# eboardPapyFeederV2_1.net
KiCad netlist of a schematic drawn in Altium Designer
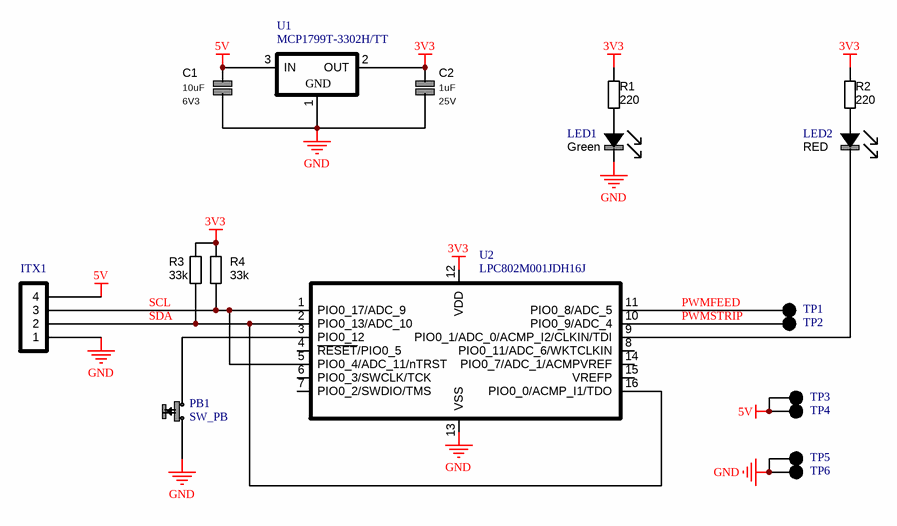
[diagram p0: eboardPapyFeederV2.1.SchDoc]

(export (version "E")
  (design (tool "Eeschema 10.0.6"))
  (components
    (comp (ref "C1")
      (value "10uF")
      (footprint "0603_CAP")
      (description "CAP CER 10UF 6V3 X5R 0603")
      (fields
        (field (name "VOLTAGE") "6V3")
        (field (name "MANUFACTURER") "Murata Electronics North America")
        (field (name "MANUFACTURER PART NUMBER") "GRM188R60J106ME84J")
      )
      (libsource (lib "Database_Library") (part "CAP"))
    )
    (comp (ref "C2")
      (value "1uF")
      (footprint "0603_CAP")
      (description "CAP CER 1uF 25V X5R 0603")
      (fields
        (field (name "VOLTAGE") "25V")
        (field (name "MANUFACTURER") "YAGEO")
        (field (name "MANUFACTURER PART NUMBER") "CC0603KRX5R8BB105")
      )
      (libsource (lib "Database_Library") (part "CAP"))
    )
    (comp (ref "ITX1")
      (value "Header 01X04")
      (footprint "HEADER_1X4_2MM_SPRING_01")
      (description "4POS spring connector")
      (fields (field (name "MANUFACTURER") "MOLEX") (field (name "MANUFACTURER PART NUMBER") "472861001"))
      (libsource (lib "Database_Library") (part "Header 01X04"))
    )
    (comp (ref "LED1")
      (value "Green")
      (footprint "0603_LED")
      (description "LED Green 0603")
      (fields
        (field (name "COLOR") "Green")
        (field (name "MANUFACTURER") "Dialight")
        (field (name "MANUFACTURER PART NUMBER") "599-0081-007F")
      )
      (libsource (lib "Database_Library") (part "LED"))
    )
    (comp (ref "LED2")
      (value "RED")
      (footprint "0603_LED")
      (description "LED RED 0603")
      (fields
        (field (name "COLOR") "RED")
        (field (name "MANUFACTURER") "Dialight")
        (field (name "MANUFACTURER PART NUMBER") "599-0010-007F")
      )
      (libsource (lib "Database_Library") (part "LED"))
    )
    (comp (ref "PB1")
      (value "SW_PB")
      (footprint "SKRPABE010")
      (description "Mini momentary push button")
      (fields (field (name "MANUFACTURER") "ALPS") (field (name "MANUFACTURER PART NUMBER") "SKRPABE010"))
      (libsource (lib "Database_Library") (part "SW_PB"))
    )
    (comp (ref "R1")
      (value "220")
      (footprint "0603_RES")
      (description "RES SMD 220 OHM 1% 1/10W 0603")
      (fields
        (field (name "MANUFACTURER") "Panasonic Electronic Components")
        (field (name "MANUFACTURER PART NUMBER") "ERJ-3EKF2200V")
      )
      (libsource (lib "Database_Library") (part "RES"))
    )
    (comp (ref "R2")
      (value "220")
      (footprint "0603_RES")
      (description "RES SMD 220 OHM 1% 1/10W 0603")
      (fields
        (field (name "MANUFACTURER") "Panasonic Electronic Components")
        (field (name "MANUFACTURER PART NUMBER") "ERJ-3EKF2200V")
      )
      (libsource (lib "Database_Library") (part "RES"))
    )
    (comp (ref "R3")
      (value "33k")
      (footprint "0603_RES")
      (description "RES SMD 33K OHM 1% 1/10W 0603")
      (fields
        (field (name "MANUFACTURER") "Panasonic Electronic Components")
        (field (name "MANUFACTURER PART NUMBER") "ERJ-3EKF3302V")
      )
      (libsource (lib "Database_Library") (part "RES"))
    )
    (comp (ref "R4")
      (value "33k")
      (footprint "0603_RES")
      (description "RES SMD 33K OHM 1% 1/10W 0603")
      (fields
        (field (name "MANUFACTURER") "Panasonic Electronic Components")
        (field (name "MANUFACTURER PART NUMBER") "ERJ-3EKF3302V")
      )
      (libsource (lib "Database_Library") (part "RES"))
    )
    (comp (ref "TP1")
      (value "TP")
      (footprint "PAD_TOP_1x5_REC")
      (description "PAD_1x5_REC")
      (fields (field (name "MANUFACTURER") "None"))
      (libsource (lib "Database_Library") (part "TP"))
    )
    (comp (ref "TP2")
      (value "TP")
      (footprint "PAD_TOP_1x5_REC")
      (description "PAD_1x5_REC")
      (fields (field (name "MANUFACTURER") "None"))
      (libsource (lib "Database_Library") (part "TP"))
    )
    (comp (ref "TP3")
      (value "TP")
      (footprint "PAD_TOP_1x5_REC")
      (description "PAD_1x5_REC")
      (fields (field (name "MANUFACTURER") "None"))
      (libsource (lib "Database_Library") (part "TP"))
    )
    (comp (ref "TP4")
      (value "TP")
      (footprint "PAD_TOP_1x5_REC")
      (description "PAD_1x5_REC")
      (fields (field (name "MANUFACTURER") "None"))
      (libsource (lib "Database_Library") (part "TP"))
    )
    (comp (ref "TP5")
      (value "TP")
      (footprint "PAD_TOP_1x5_REC")
      (description "PAD_1x5_REC")
      (fields (field (name "MANUFACTURER") "None"))
      (libsource (lib "Database_Library") (part "TP"))
    )
    (comp (ref "TP6")
      (value "TP")
      (footprint "PAD_TOP_1x5_REC")
      (description "PAD_1x5_REC")
      (fields (field (name "MANUFACTURER") "None"))
      (libsource (lib "Database_Library") (part "TP"))
    )
    (comp (ref "U1")
      (value "3P-Fixed_GND_VOUT_VIN")
      (footprint "SOT95P237X112-3N")
      (description "LDO 3V3 80mA")
      (fields
        (field (name "MANUFACTURER") "MICROCHIP")
        (field (name "MANUFACTURER PART NUMBER") "MCP1799T-3302H/TT")
      )
      (libsource (lib "Database_Library") (part "3P-Fixed_GND_VOUT_VIN"))
    )
    (comp (ref "U2")
      (value "LPC802M001JDH16J")
      (footprint "SOP65P640X110-16M")
      (description "ARM Cortex M0+")
      (fields (field (name "MANUFACTURER") "NXP") (field (name "VOLTAGE") "3.3V"))
      (libsource (lib "Database_Library") (part "LPC802M001JDH16J"))
    )
  )
  (nets
    (net (code "1") (name "/PWMFEED") (class "Default")
      (node (ref "TP1") (pin "1") (pintype "passive"))
      (node (ref "U2") (pin "11") (pinfunction "PIO0_8/ADC_5_11") (pintype "passive"))
    )
    (net (code "2") (name "/PWMSTRIP") (class "Default")
      (node (ref "TP2") (pin "1") (pintype "passive"))
      (node (ref "U2") (pin "10") (pinfunction "PIO0_9/ADC_4_10") (pintype "passive"))
    )
    (net (code "3") (name "/SCL") (class "Default")
      (node (ref "ITX1") (pin "3") (pinfunction "3_3") (pintype "passive"))
      (node (ref "R4") (pin "1") (pinfunction "1_1") (pintype "passive"))
      (node (ref "U2") (pin "1") (pinfunction "PIO0_17/ADC_9_1") (pintype "passive"))
      (node (ref "U2") (pin "5") (pinfunction "PIO0_4/ADC_11/nTRST_5") (pintype "passive"))
    )
    (net (code "4") (name "/SDA") (class "Default")
      (node (ref "ITX1") (pin "2") (pinfunction "2_2") (pintype "passive"))
      (node (ref "R3") (pin "1") (pinfunction "1_1") (pintype "passive"))
      (node (ref "U2") (pin "16") (pinfunction "PIO0_0/ACMP_I1/TDO_16") (pintype "passive"))
      (node (ref "U2") (pin "2") (pinfunction "PIO0_13/ADC_10_2") (pintype "passive"))
    )
    (net (code "5") (name "3V3") (class "Default")
      (node (ref "C2") (pin "1") (pinfunction "1_1") (pintype "passive"))
      (node (ref "R1") (pin "2") (pinfunction "2_2") (pintype "passive"))
      (node (ref "R2") (pin "2") (pinfunction "2_2") (pintype "passive"))
      (node (ref "R3") (pin "2") (pinfunction "2_2") (pintype "passive"))
      (node (ref "R4") (pin "2") (pinfunction "2_2") (pintype "passive"))
      (node (ref "U1") (pin "2") (pinfunction "OUT_2") (pintype "power_in"))
      (node (ref "U2") (pin "12") (pinfunction "VDD_12") (pintype "passive"))
    )
    (net (code "6") (name "5V") (class "Default")
      (node (ref "C1") (pin "1") (pinfunction "1_1") (pintype "passive"))
      (node (ref "ITX1") (pin "4") (pinfunction "4_4") (pintype "passive"))
      (node (ref "TP3") (pin "1") (pintype "passive"))
      (node (ref "TP4") (pin "1") (pintype "passive"))
      (node (ref "U1") (pin "3") (pinfunction "IN_3") (pintype "power_in"))
    )
    (net (code "7") (name "GND") (class "Default")
      (node (ref "C1") (pin "2") (pinfunction "2_2") (pintype "passive"))
      (node (ref "C2") (pin "2") (pinfunction "2_2") (pintype "passive"))
      (node (ref "ITX1") (pin "1") (pinfunction "1_1") (pintype "passive"))
      (node (ref "LED1") (pin "2") (pinfunction "K_2") (pintype "passive"))
      (node (ref "PB1") (pin "1") (pintype "passive"))
      (node (ref "TP5") (pin "1") (pintype "passive"))
      (node (ref "TP6") (pin "1") (pintype "passive"))
      (node (ref "U1") (pin "1") (pinfunction "GND_1") (pintype "power_in"))
      (node (ref "U2") (pin "13") (pinfunction "VSS_13") (pintype "passive"))
    )
    (net (code "8") (name "Net-(LED1-A)") (class "Default")
      (node (ref "LED1") (pin "1") (pinfunction "A_1") (pintype "passive"))
      (node (ref "R1") (pin "1") (pinfunction "1_1") (pintype "passive"))
    )
    (net (code "9") (name "Net-(LED2-A)") (class "Default")
      (node (ref "LED2") (pin "1") (pinfunction "A_1") (pintype "passive"))
      (node (ref "R2") (pin "1") (pinfunction "1_1") (pintype "passive"))
    )
    (net (code "10") (name "Net-(LED2-K)") (class "Default")
      (node (ref "LED2") (pin "2") (pinfunction "K_2") (pintype "passive"))
      (node (ref "U2") (pin "9") (pinfunction "PIO0_1/ADC_0/ACMP_I2/CLKIN/TDI_9") (pintype "passive"))
    )
    (net (code "11") (name "Net-(U2-PIO0_12)") (class "Default")
      (node (ref "PB1") (pin "2") (pintype "passive"))
      (node (ref "U2") (pin "3") (pinfunction "PIO0_12_3") (pintype "passive"))
    )
    (net (code "12") (name "unconnected-(U2-PIO0_2{slash}SWDIO{slash}TMS-Pad7)") (class "Default")
      (node (ref "U2") (pin "7") (pinfunction "PIO0_2/SWDIO/TMS_7") (pintype "passive"))
    )
    (net (code "13") (name "unconnected-(U2-PIO0_3{slash}SWCLK{slash}TCK-Pad6)") (class "Default")
      (node (ref "U2") (pin "6") (pinfunction "PIO0_3/SWCLK/TCK_6") (pintype "passive"))
    )
    (net (code "14") (name "unconnected-(U2-PIO0_7{slash}ADC_1{slash}ACMPVREF-Pad14)") (class "Default")
      (node (ref "U2") (pin "14") (pinfunction "PIO0_7/ADC_1/ACMPVREF_14") (pintype "passive"))
    )
    (net (code "15") (name "unconnected-(U2-PIO0_11{slash}ADC_6{slash}WKTCLKIN-Pad8)") (class "Default")
      (node (ref "U2") (pin "8") (pinfunction "PIO0_11/ADC_6/WKTCLKIN_8") (pintype "passive"))
    )
    (net (code "16") (name "unconnected-(U2-VREFP-Pad15)") (class "Default")
      (node (ref "U2") (pin "15") (pinfunction "VREFP_15") (pintype "passive"))
    )
    (net (code "17") (name "unconnected-(U2-~{RESET}{slash}PIO0_5-Pad4)") (class "Default")
      (node (ref "U2") (pin "4") (pinfunction "~{RESET}/PIO0_5_4") (pintype "passive"))
    )
  )
)
